# collision.net
KiCad netlist of a schematic drawn in EAGLE
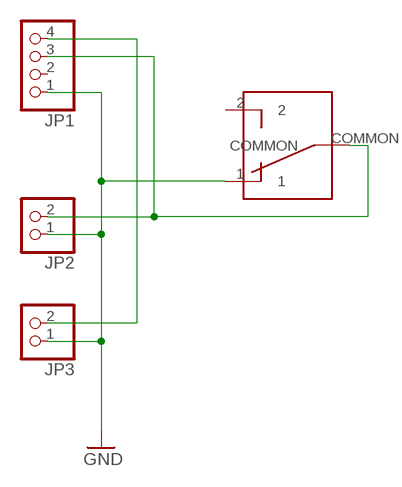
[diagram p0: schematic, sheet 1]

(export (version "E")
  (design (tool "Eeschema 10.0.6"))
  (components
    (comp (ref "JP1")
      (value "PINHD-1X4/90")
      (footprint "eagle-import:1X04_90")
      (libsource (lib "eagle-import") (part "PINHD-1X4/90"))
    )
    (comp (ref "JP2")
      (value "PINHD-1X2/90")
      (footprint "eagle-import:1X02_90")
      (libsource (lib "eagle-import") (part "PINHD-1X2/90"))
    )
    (comp (ref "JP3")
      (value "PINHD-1X2/90")
      (footprint "eagle-import:1X02_90")
      (libsource (lib "eagle-import") (part "PINHD-1X2/90"))
    )
    (comp (ref "U$1")
      (value "LEVER_SWITCH")
      (footprint "eagle-import:LEVER_SWITCH")
      (libsource (lib "eagle-import") (part "LEVER_SWITCH"))
    )
  )
  (nets
    (net (code "1") (name "GND") (class "Default")
      (node (ref "JP1") (pin "1") (pinfunction "1_1") (pintype "passive"))
      (node (ref "JP2") (pin "1") (pinfunction "1_1") (pintype "passive"))
      (node (ref "JP3") (pin "1") (pinfunction "1_1") (pintype "passive"))
      (node (ref "U$1") (pin "1") (pinfunction "1_1") (pintype "bidirectional"))
    )
    (net (code "2") (name "Net-(JP1-Pad3)") (class "Default")
      (node (ref "JP1") (pin "3") (pinfunction "3_3") (pintype "passive"))
      (node (ref "JP2") (pin "2") (pinfunction "2_2") (pintype "passive"))
      (node (ref "U$1") (pin "COMMON") (pinfunction "COMMON_COMMON") (pintype "bidirectional"))
    )
    (net (code "3") (name "Net-(JP1-Pad4)") (class "Default")
      (node (ref "JP1") (pin "4") (pinfunction "4_4") (pintype "passive"))
      (node (ref "JP3") (pin "2") (pinfunction "2_2") (pintype "passive"))
    )
    (net (code "4") (name "unconnected-(JP1-Pad2)") (class "Default")
      (node (ref "JP1") (pin "2") (pinfunction "2_2") (pintype "passive"))
    )
    (net (code "5") (name "unconnected-(U$1-Pad2)") (class "Default")
      (node (ref "U$1") (pin "2") (pinfunction "2_2") (pintype "bidirectional"))
    )
  )
)
